# Backplane.net
KiCad netlist of a schematic drawn in EAGLE
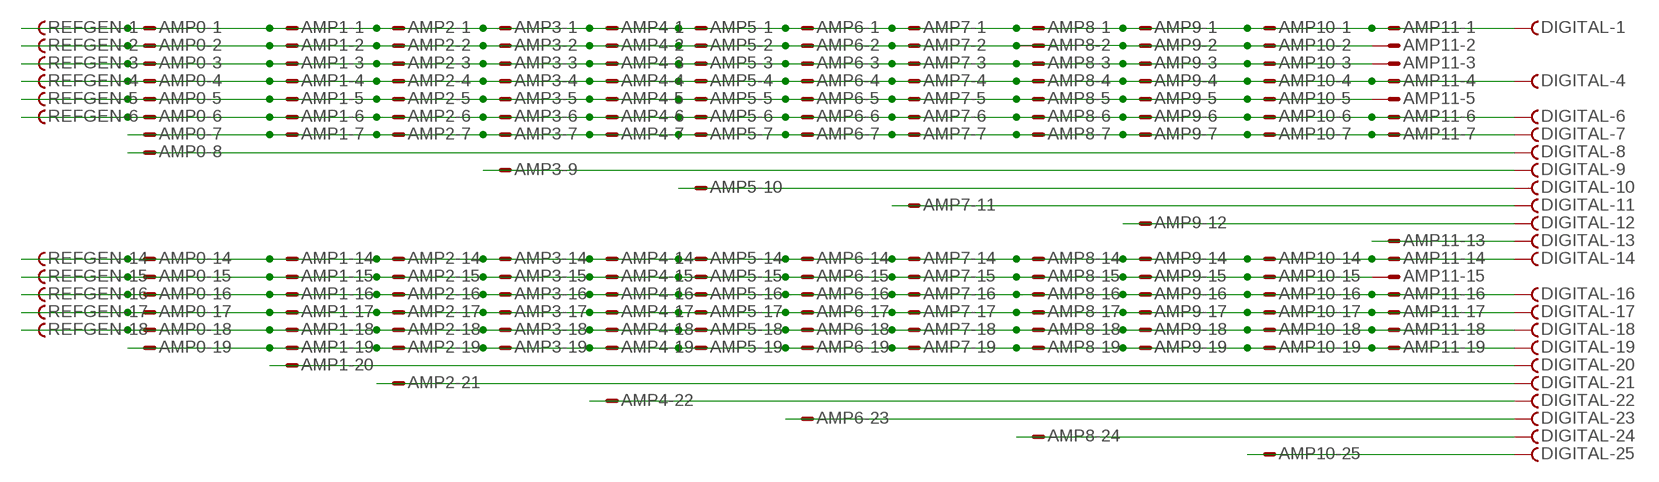
[diagram p0: schematic, sheet 1]

(export (version "E")
  (design (tool "Eeschema 10.0.6"))
  (components
    (comp (ref "AMP0")
      (value "M25VPS")
      (footprint "eagle-import:M25VP")
      (libsource (lib "eagle-import") (part "M25?SVP"))
    )
    (comp (ref "AMP1")
      (value "M25VPS")
      (footprint "eagle-import:M25VP")
      (libsource (lib "eagle-import") (part "M25?SVP"))
    )
    (comp (ref "AMP2")
      (value "M25VPS")
      (footprint "eagle-import:M25VP")
      (libsource (lib "eagle-import") (part "M25?SVP"))
    )
    (comp (ref "AMP3")
      (value "M25VPS")
      (footprint "eagle-import:M25VP")
      (libsource (lib "eagle-import") (part "M25?SVP"))
    )
    (comp (ref "AMP4")
      (value "M25VPS")
      (footprint "eagle-import:M25VP")
      (libsource (lib "eagle-import") (part "M25?SVP"))
    )
    (comp (ref "AMP5")
      (value "M25VPS")
      (footprint "eagle-import:M25VP")
      (libsource (lib "eagle-import") (part "M25?SVP"))
    )
    (comp (ref "AMP6")
      (value "M25VPS")
      (footprint "eagle-import:M25VP")
      (libsource (lib "eagle-import") (part "M25?SVP"))
    )
    (comp (ref "AMP7")
      (value "M25VPS")
      (footprint "eagle-import:M25VP")
      (libsource (lib "eagle-import") (part "M25?SVP"))
    )
    (comp (ref "AMP8")
      (value "M25VPS")
      (footprint "eagle-import:M25VP")
      (libsource (lib "eagle-import") (part "M25?SVP"))
    )
    (comp (ref "AMP9")
      (value "M25VPS")
      (footprint "eagle-import:M25VP")
      (libsource (lib "eagle-import") (part "M25?SVP"))
    )
    (comp (ref "AMP10")
      (value "M25VPS")
      (footprint "eagle-import:M25VP")
      (libsource (lib "eagle-import") (part "M25?SVP"))
    )
    (comp (ref "AMP11")
      (value "M25VPS")
      (footprint "eagle-import:M25VP")
      (libsource (lib "eagle-import") (part "M25?SVP"))
    )
    (comp (ref "DIGITAL")
      (value "F25VPS")
      (footprint "eagle-import:F25VP")
      (libsource (lib "eagle-import") (part "F25?SVP"))
    )
    (comp (ref "REFGEN")
      (value "F25VPS")
      (footprint "eagle-import:F25VP")
      (libsource (lib "eagle-import") (part "F25?SVP"))
    )
  )
  (nets
    (net (code "1") (name "Net-(AMP0A-M)") (class "Default")
      (node (ref "AMP0") (pin "1") (pinfunction "M_1") (pintype "passive"))
      (node (ref "AMP1") (pin "1") (pinfunction "M_1") (pintype "passive"))
      (node (ref "AMP10") (pin "1") (pinfunction "M_1") (pintype "passive"))
      (node (ref "AMP11") (pin "1") (pinfunction "M_1") (pintype "passive"))
      (node (ref "AMP2") (pin "1") (pinfunction "M_1") (pintype "passive"))
      (node (ref "AMP3") (pin "1") (pinfunction "M_1") (pintype "passive"))
      (node (ref "AMP4") (pin "1") (pinfunction "M_1") (pintype "passive"))
      (node (ref "AMP5") (pin "1") (pinfunction "M_1") (pintype "passive"))
      (node (ref "AMP6") (pin "1") (pinfunction "M_1") (pintype "passive"))
      (node (ref "AMP7") (pin "1") (pinfunction "M_1") (pintype "passive"))
      (node (ref "AMP8") (pin "1") (pinfunction "M_1") (pintype "passive"))
      (node (ref "AMP9") (pin "1") (pinfunction "M_1") (pintype "passive"))
      (node (ref "DIGITAL") (pin "1") (pinfunction "F_1") (pintype "passive"))
      (node (ref "REFGEN") (pin "1") (pinfunction "F_1") (pintype "passive"))
    )
    (net (code "2") (name "Net-(AMP0F-M)") (class "Default")
      (node (ref "AMP0") (pin "14") (pinfunction "M_14") (pintype "passive"))
      (node (ref "AMP1") (pin "14") (pinfunction "M_14") (pintype "passive"))
      (node (ref "AMP10") (pin "14") (pinfunction "M_14") (pintype "passive"))
      (node (ref "AMP11") (pin "14") (pinfunction "M_14") (pintype "passive"))
      (node (ref "AMP2") (pin "14") (pinfunction "M_14") (pintype "passive"))
      (node (ref "AMP3") (pin "14") (pinfunction "M_14") (pintype "passive"))
      (node (ref "AMP4") (pin "14") (pinfunction "M_14") (pintype "passive"))
      (node (ref "AMP5") (pin "14") (pinfunction "M_14") (pintype "passive"))
      (node (ref "AMP6") (pin "14") (pinfunction "M_14") (pintype "passive"))
      (node (ref "AMP7") (pin "14") (pinfunction "M_14") (pintype "passive"))
      (node (ref "AMP8") (pin "14") (pinfunction "M_14") (pintype "passive"))
      (node (ref "AMP9") (pin "14") (pinfunction "M_14") (pintype "passive"))
      (node (ref "DIGITAL") (pin "14") (pinfunction "F_14") (pintype "passive"))
      (node (ref "REFGEN") (pin "14") (pinfunction "F_14") (pintype "passive"))
    )
    (net (code "3") (name "Net-(AMP0G-M)") (class "Default")
      (node (ref "AMP0") (pin "15") (pinfunction "M_15") (pintype "passive"))
      (node (ref "AMP1") (pin "15") (pinfunction "M_15") (pintype "passive"))
      (node (ref "AMP10") (pin "15") (pinfunction "M_15") (pintype "passive"))
      (node (ref "AMP11") (pin "15") (pinfunction "M_15") (pintype "passive"))
      (node (ref "AMP2") (pin "15") (pinfunction "M_15") (pintype "passive"))
      (node (ref "AMP3") (pin "15") (pinfunction "M_15") (pintype "passive"))
      (node (ref "AMP4") (pin "15") (pinfunction "M_15") (pintype "passive"))
      (node (ref "AMP5") (pin "15") (pinfunction "M_15") (pintype "passive"))
      (node (ref "AMP6") (pin "15") (pinfunction "M_15") (pintype "passive"))
      (node (ref "AMP7") (pin "15") (pinfunction "M_15") (pintype "passive"))
      (node (ref "AMP8") (pin "15") (pinfunction "M_15") (pintype "passive"))
      (node (ref "AMP9") (pin "15") (pinfunction "M_15") (pintype "passive"))
      (node (ref "REFGEN") (pin "15") (pinfunction "F_15") (pintype "passive"))
    )
    (net (code "4") (name "Net-(AMP0H-M)") (class "Default")
      (node (ref "AMP0") (pin "16") (pinfunction "M_16") (pintype "passive"))
      (node (ref "AMP1") (pin "16") (pinfunction "M_16") (pintype "passive"))
      (node (ref "AMP10") (pin "16") (pinfunction "M_16") (pintype "passive"))
      (node (ref "AMP11") (pin "16") (pinfunction "M_16") (pintype "passive"))
      (node (ref "AMP2") (pin "16") (pinfunction "M_16") (pintype "passive"))
      (node (ref "AMP3") (pin "16") (pinfunction "M_16") (pintype "passive"))
      (node (ref "AMP4") (pin "16") (pinfunction "M_16") (pintype "passive"))
      (node (ref "AMP5") (pin "16") (pinfunction "M_16") (pintype "passive"))
      (node (ref "AMP6") (pin "16") (pinfunction "M_16") (pintype "passive"))
      (node (ref "AMP7") (pin "16") (pinfunction "M_16") (pintype "passive"))
      (node (ref "AMP8") (pin "16") (pinfunction "M_16") (pintype "passive"))
      (node (ref "AMP9") (pin "16") (pinfunction "M_16") (pintype "passive"))
      (node (ref "DIGITAL") (pin "16") (pinfunction "F_16") (pintype "passive"))
      (node (ref "REFGEN") (pin "16") (pinfunction "F_16") (pintype "passive"))
    )
    (net (code "5") (name "Net-(AMP0I-M)") (class "Default")
      (node (ref "AMP0") (pin "17") (pinfunction "M_17") (pintype "passive"))
      (node (ref "AMP1") (pin "17") (pinfunction "M_17") (pintype "passive"))
      (node (ref "AMP10") (pin "17") (pinfunction "M_17") (pintype "passive"))
      (node (ref "AMP11") (pin "17") (pinfunction "M_17") (pintype "passive"))
      (node (ref "AMP2") (pin "17") (pinfunction "M_17") (pintype "passive"))
      (node (ref "AMP3") (pin "17") (pinfunction "M_17") (pintype "passive"))
      (node (ref "AMP4") (pin "17") (pinfunction "M_17") (pintype "passive"))
      (node (ref "AMP5") (pin "17") (pinfunction "M_17") (pintype "passive"))
      (node (ref "AMP6") (pin "17") (pinfunction "M_17") (pintype "passive"))
      (node (ref "AMP7") (pin "17") (pinfunction "M_17") (pintype "passive"))
      (node (ref "AMP8") (pin "17") (pinfunction "M_17") (pintype "passive"))
      (node (ref "AMP9") (pin "17") (pinfunction "M_17") (pintype "passive"))
      (node (ref "DIGITAL") (pin "17") (pinfunction "F_17") (pintype "passive"))
      (node (ref "REFGEN") (pin "17") (pinfunction "F_17") (pintype "passive"))
    )
    (net (code "6") (name "Net-(AMP0J-M)") (class "Default")
      (node (ref "AMP0") (pin "18") (pinfunction "M_18") (pintype "passive"))
      (node (ref "AMP1") (pin "18") (pinfunction "M_18") (pintype "passive"))
      (node (ref "AMP10") (pin "18") (pinfunction "M_18") (pintype "passive"))
      (node (ref "AMP11") (pin "18") (pinfunction "M_18") (pintype "passive"))
      (node (ref "AMP2") (pin "18") (pinfunction "M_18") (pintype "passive"))
      (node (ref "AMP3") (pin "18") (pinfunction "M_18") (pintype "passive"))
      (node (ref "AMP4") (pin "18") (pinfunction "M_18") (pintype "passive"))
      (node (ref "AMP5") (pin "18") (pinfunction "M_18") (pintype "passive"))
      (node (ref "AMP6") (pin "18") (pinfunction "M_18") (pintype "passive"))
      (node (ref "AMP7") (pin "18") (pinfunction "M_18") (pintype "passive"))
      (node (ref "AMP8") (pin "18") (pinfunction "M_18") (pintype "passive"))
      (node (ref "AMP9") (pin "18") (pinfunction "M_18") (pintype "passive"))
      (node (ref "DIGITAL") (pin "18") (pinfunction "F_18") (pintype "passive"))
      (node (ref "REFGEN") (pin "18") (pinfunction "F_18") (pintype "passive"))
    )
    (net (code "7") (name "Net-(AMP0K-M)") (class "Default")
      (node (ref "AMP0") (pin "19") (pinfunction "M_19") (pintype "passive"))
      (node (ref "AMP1") (pin "19") (pinfunction "M_19") (pintype "passive"))
      (node (ref "AMP10") (pin "19") (pinfunction "M_19") (pintype "passive"))
      (node (ref "AMP11") (pin "19") (pinfunction "M_19") (pintype "passive"))
      (node (ref "AMP2") (pin "19") (pinfunction "M_19") (pintype "passive"))
      (node (ref "AMP3") (pin "19") (pinfunction "M_19") (pintype "passive"))
      (node (ref "AMP4") (pin "19") (pinfunction "M_19") (pintype "passive"))
      (node (ref "AMP5") (pin "19") (pinfunction "M_19") (pintype "passive"))
      (node (ref "AMP6") (pin "19") (pinfunction "M_19") (pintype "passive"))
      (node (ref "AMP7") (pin "19") (pinfunction "M_19") (pintype "passive"))
      (node (ref "AMP8") (pin "19") (pinfunction "M_19") (pintype "passive"))
      (node (ref "AMP9") (pin "19") (pinfunction "M_19") (pintype "passive"))
      (node (ref "DIGITAL") (pin "19") (pinfunction "F_19") (pintype "passive"))
    )
    (net (code "8") (name "Net-(AMP0L-M)") (class "Default")
      (node (ref "AMP0") (pin "2") (pinfunction "M_2") (pintype "passive"))
      (node (ref "AMP1") (pin "2") (pinfunction "M_2") (pintype "passive"))
      (node (ref "AMP10") (pin "2") (pinfunction "M_2") (pintype "passive"))
      (node (ref "AMP11") (pin "2") (pinfunction "M_2") (pintype "passive"))
      (node (ref "AMP2") (pin "2") (pinfunction "M_2") (pintype "passive"))
      (node (ref "AMP3") (pin "2") (pinfunction "M_2") (pintype "passive"))
      (node (ref "AMP4") (pin "2") (pinfunction "M_2") (pintype "passive"))
      (node (ref "AMP5") (pin "2") (pinfunction "M_2") (pintype "passive"))
      (node (ref "AMP6") (pin "2") (pinfunction "M_2") (pintype "passive"))
      (node (ref "AMP7") (pin "2") (pinfunction "M_2") (pintype "passive"))
      (node (ref "AMP8") (pin "2") (pinfunction "M_2") (pintype "passive"))
      (node (ref "AMP9") (pin "2") (pinfunction "M_2") (pintype "passive"))
      (node (ref "REFGEN") (pin "2") (pinfunction "F_2") (pintype "passive"))
    )
    (net (code "9") (name "Net-(AMP0S-M)") (class "Default")
      (node (ref "AMP0") (pin "3") (pinfunction "M_3") (pintype "passive"))
      (node (ref "AMP1") (pin "3") (pinfunction "M_3") (pintype "passive"))
      (node (ref "AMP10") (pin "3") (pinfunction "M_3") (pintype "passive"))
      (node (ref "AMP11") (pin "3") (pinfunction "M_3") (pintype "passive"))
      (node (ref "AMP2") (pin "3") (pinfunction "M_3") (pintype "passive"))
      (node (ref "AMP3") (pin "3") (pinfunction "M_3") (pintype "passive"))
      (node (ref "AMP4") (pin "3") (pinfunction "M_3") (pintype "passive"))
      (node (ref "AMP5") (pin "3") (pinfunction "M_3") (pintype "passive"))
      (node (ref "AMP6") (pin "3") (pinfunction "M_3") (pintype "passive"))
      (node (ref "AMP7") (pin "3") (pinfunction "M_3") (pintype "passive"))
      (node (ref "AMP8") (pin "3") (pinfunction "M_3") (pintype "passive"))
      (node (ref "AMP9") (pin "3") (pinfunction "M_3") (pintype "passive"))
      (node (ref "REFGEN") (pin "3") (pinfunction "F_3") (pintype "passive"))
    )
    (net (code "10") (name "Net-(AMP0T-M)") (class "Default")
      (node (ref "AMP0") (pin "4") (pinfunction "M_4") (pintype "passive"))
      (node (ref "AMP1") (pin "4") (pinfunction "M_4") (pintype "passive"))
      (node (ref "AMP10") (pin "4") (pinfunction "M_4") (pintype "passive"))
      (node (ref "AMP11") (pin "4") (pinfunction "M_4") (pintype "passive"))
      (node (ref "AMP2") (pin "4") (pinfunction "M_4") (pintype "passive"))
      (node (ref "AMP3") (pin "4") (pinfunction "M_4") (pintype "passive"))
      (node (ref "AMP4") (pin "4") (pinfunction "M_4") (pintype "passive"))
      (node (ref "AMP5") (pin "4") (pinfunction "M_4") (pintype "passive"))
      (node (ref "AMP6") (pin "4") (pinfunction "M_4") (pintype "passive"))
      (node (ref "AMP7") (pin "4") (pinfunction "M_4") (pintype "passive"))
      (node (ref "AMP8") (pin "4") (pinfunction "M_4") (pintype "passive"))
      (node (ref "AMP9") (pin "4") (pinfunction "M_4") (pintype "passive"))
      (node (ref "DIGITAL") (pin "4") (pinfunction "F_4") (pintype "passive"))
      (node (ref "REFGEN") (pin "4") (pinfunction "F_4") (pintype "passive"))
    )
    (net (code "11") (name "Net-(AMP0U-M)") (class "Default")
      (node (ref "AMP0") (pin "5") (pinfunction "M_5") (pintype "passive"))
      (node (ref "AMP1") (pin "5") (pinfunction "M_5") (pintype "passive"))
      (node (ref "AMP10") (pin "5") (pinfunction "M_5") (pintype "passive"))
      (node (ref "AMP11") (pin "5") (pinfunction "M_5") (pintype "passive"))
      (node (ref "AMP2") (pin "5") (pinfunction "M_5") (pintype "passive"))
      (node (ref "AMP3") (pin "5") (pinfunction "M_5") (pintype "passive"))
      (node (ref "AMP4") (pin "5") (pinfunction "M_5") (pintype "passive"))
      (node (ref "AMP5") (pin "5") (pinfunction "M_5") (pintype "passive"))
      (node (ref "AMP6") (pin "5") (pinfunction "M_5") (pintype "passive"))
      (node (ref "AMP7") (pin "5") (pinfunction "M_5") (pintype "passive"))
      (node (ref "AMP8") (pin "5") (pinfunction "M_5") (pintype "passive"))
      (node (ref "AMP9") (pin "5") (pinfunction "M_5") (pintype "passive"))
      (node (ref "REFGEN") (pin "5") (pinfunction "F_5") (pintype "passive"))
    )
    (net (code "12") (name "Net-(AMP0V-M)") (class "Default")
      (node (ref "AMP0") (pin "6") (pinfunction "M_6") (pintype "passive"))
      (node (ref "AMP1") (pin "6") (pinfunction "M_6") (pintype "passive"))
      (node (ref "AMP10") (pin "6") (pinfunction "M_6") (pintype "passive"))
      (node (ref "AMP11") (pin "6") (pinfunction "M_6") (pintype "passive"))
      (node (ref "AMP2") (pin "6") (pinfunction "M_6") (pintype "passive"))
      (node (ref "AMP3") (pin "6") (pinfunction "M_6") (pintype "passive"))
      (node (ref "AMP4") (pin "6") (pinfunction "M_6") (pintype "passive"))
      (node (ref "AMP5") (pin "6") (pinfunction "M_6") (pintype "passive"))
      (node (ref "AMP6") (pin "6") (pinfunction "M_6") (pintype "passive"))
      (node (ref "AMP7") (pin "6") (pinfunction "M_6") (pintype "passive"))
      (node (ref "AMP8") (pin "6") (pinfunction "M_6") (pintype "passive"))
      (node (ref "AMP9") (pin "6") (pinfunction "M_6") (pintype "passive"))
      (node (ref "DIGITAL") (pin "6") (pinfunction "F_6") (pintype "passive"))
      (node (ref "REFGEN") (pin "6") (pinfunction "F_6") (pintype "passive"))
    )
    (net (code "13") (name "Net-(AMP0W-M)") (class "Default")
      (node (ref "AMP0") (pin "7") (pinfunction "M_7") (pintype "passive"))
      (node (ref "AMP1") (pin "7") (pinfunction "M_7") (pintype "passive"))
      (node (ref "AMP10") (pin "7") (pinfunction "M_7") (pintype "passive"))
      (node (ref "AMP11") (pin "7") (pinfunction "M_7") (pintype "passive"))
      (node (ref "AMP2") (pin "7") (pinfunction "M_7") (pintype "passive"))
      (node (ref "AMP3") (pin "7") (pinfunction "M_7") (pintype "passive"))
      (node (ref "AMP4") (pin "7") (pinfunction "M_7") (pintype "passive"))
      (node (ref "AMP5") (pin "7") (pinfunction "M_7") (pintype "passive"))
      (node (ref "AMP6") (pin "7") (pinfunction "M_7") (pintype "passive"))
      (node (ref "AMP7") (pin "7") (pinfunction "M_7") (pintype "passive"))
      (node (ref "AMP8") (pin "7") (pinfunction "M_7") (pintype "passive"))
      (node (ref "AMP9") (pin "7") (pinfunction "M_7") (pintype "passive"))
      (node (ref "DIGITAL") (pin "7") (pinfunction "F_7") (pintype "passive"))
    )
    (net (code "14") (name "Net-(AMP0X-M)") (class "Default")
      (node (ref "AMP0") (pin "8") (pinfunction "M_8") (pintype "passive"))
      (node (ref "DIGITAL") (pin "8") (pinfunction "F_8") (pintype "passive"))
    )
    (net (code "15") (name "Net-(AMP1M-M)") (class "Default")
      (node (ref "AMP1") (pin "20") (pinfunction "M_20") (pintype "passive"))
      (node (ref "DIGITAL") (pin "20") (pinfunction "F_20") (pintype "passive"))
    )
    (net (code "16") (name "Net-(AMP2N-M)") (class "Default")
      (node (ref "AMP2") (pin "21") (pinfunction "M_21") (pintype "passive"))
      (node (ref "DIGITAL") (pin "21") (pinfunction "F_21") (pintype "passive"))
    )
    (net (code "17") (name "Net-(AMP3Y-M)") (class "Default")
      (node (ref "AMP3") (pin "9") (pinfunction "M_9") (pintype "passive"))
      (node (ref "DIGITAL") (pin "9") (pinfunction "F_9") (pintype "passive"))
    )
    (net (code "18") (name "Net-(AMP4O-M)") (class "Default")
      (node (ref "AMP4") (pin "22") (pinfunction "M_22") (pintype "passive"))
      (node (ref "DIGITAL") (pin "22") (pinfunction "F_22") (pintype "passive"))
    )
    (net (code "19") (name "Net-(AMP5B-M)") (class "Default")
      (node (ref "AMP5") (pin "10") (pinfunction "M_10") (pintype "passive"))
      (node (ref "DIGITAL") (pin "10") (pinfunction "F_10") (pintype "passive"))
    )
    (net (code "20") (name "Net-(AMP6P-M)") (class "Default")
      (node (ref "AMP6") (pin "23") (pinfunction "M_23") (pintype "passive"))
      (node (ref "DIGITAL") (pin "23") (pinfunction "F_23") (pintype "passive"))
    )
    (net (code "21") (name "Net-(AMP7C-M)") (class "Default")
      (node (ref "AMP7") (pin "11") (pinfunction "M_11") (pintype "passive"))
      (node (ref "DIGITAL") (pin "11") (pinfunction "F_11") (pintype "passive"))
    )
    (net (code "22") (name "Net-(AMP8Q-M)") (class "Default")
      (node (ref "AMP8") (pin "24") (pinfunction "M_24") (pintype "passive"))
      (node (ref "DIGITAL") (pin "24") (pinfunction "F_24") (pintype "passive"))
    )
    (net (code "23") (name "Net-(AMP9D-M)") (class "Default")
      (node (ref "AMP9") (pin "12") (pinfunction "M_12") (pintype "passive"))
      (node (ref "DIGITAL") (pin "12") (pinfunction "F_12") (pintype "passive"))
    )
    (net (code "24") (name "Net-(AMP10R-M)") (class "Default")
      (node (ref "AMP10") (pin "25") (pinfunction "M_25") (pintype "passive"))
      (node (ref "DIGITAL") (pin "25") (pinfunction "F_25") (pintype "passive"))
    )
    (net (code "25") (name "Net-(AMP11E-M)") (class "Default")
      (node (ref "AMP11") (pin "13") (pinfunction "M_13") (pintype "passive"))
      (node (ref "DIGITAL") (pin "13") (pinfunction "F_13") (pintype "passive"))
    )
  )
)
